# SCH_Jafar_wiredopposite_2022-12-09.net
KiCad netlist of a schematic drawn in EasyEDA
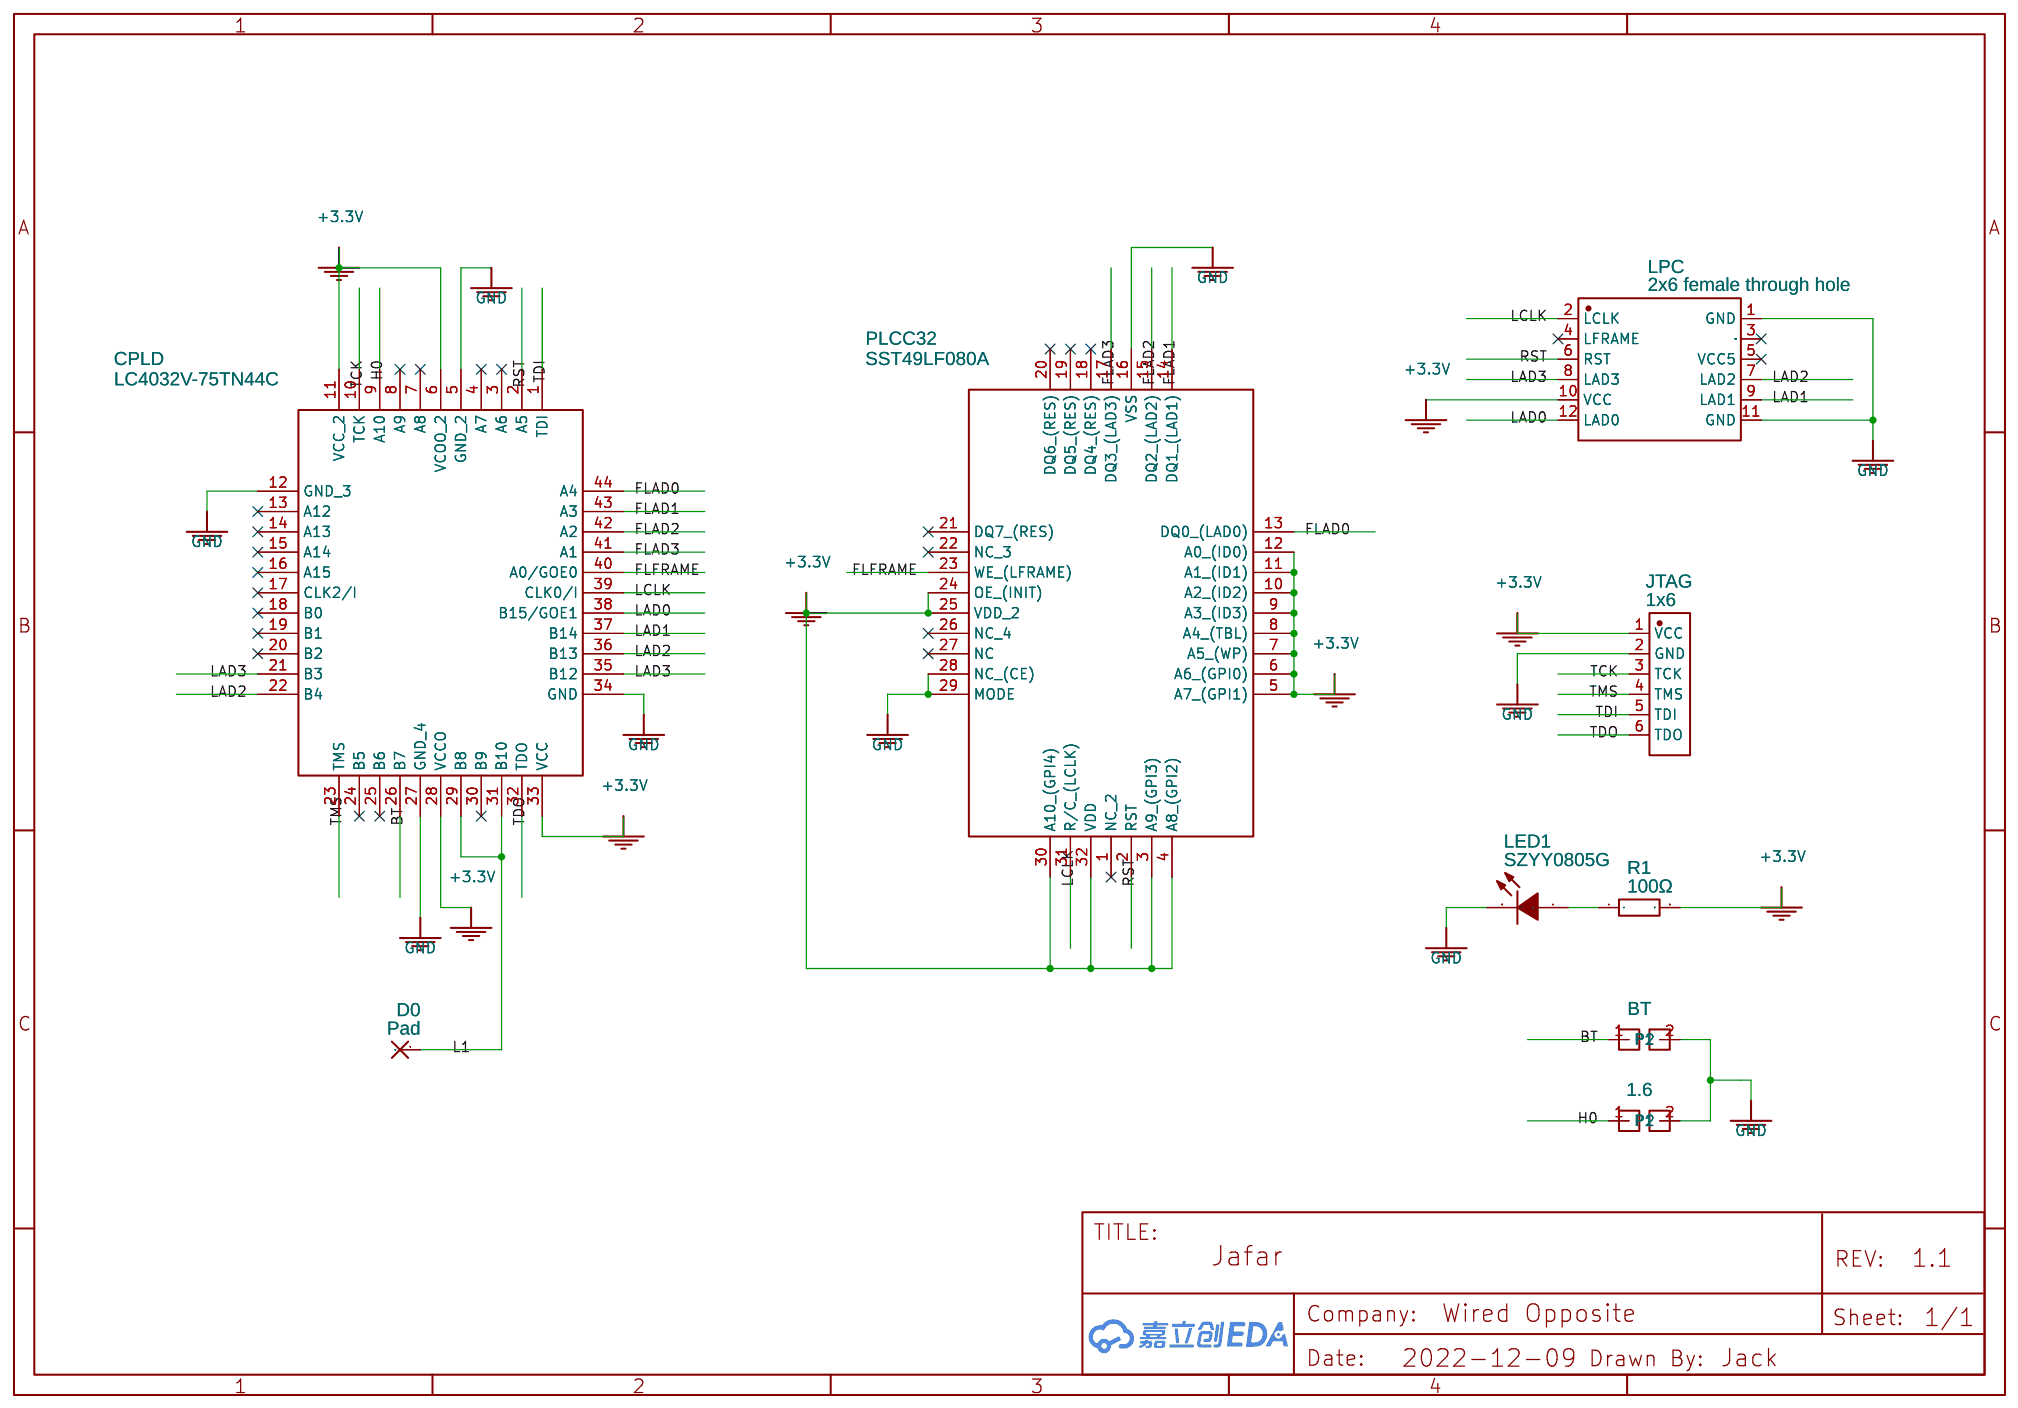
[diagram p0: schematic sheet]

(export (version "E")
  (design (tool "Eeschema 10.0.6"))
  (components
    (comp (ref "1.6") (value "2 PAD WIRE BRIDGE") (libsource (lib "") (part "2 PAD WIRE BRIDGE_1")))
    (comp (ref "BT") (value "2 PAD WIRE BRIDGE") (libsource (lib "") (part "2 PAD WIRE BRIDGE")))
    (comp (ref "CPLD") (value "LC4032V-75TN44C") (libsource (lib "") (part "LC4032V-75TN44C")))
    (comp (ref "D0") (value "Pad") (libsource (lib "") (part "WIREPADSMD5-1,8")))
    (comp (ref "JTAG")
      (value "1x6")
      (fields (field (name "BOM_Manufacturer Part") "HB3106F") (field (name "BOM_Supplier Part") "C2761399"))
      (libsource (lib "") (part "HB3106F"))
    )
    (comp (ref "LED1")
      (value "SZYY0805G")
      (fields (field (name "BOM_Supplier Part") "C434432"))
      (libsource (lib "") (part "SZYY0805G"))
    )
    (comp (ref "LPC") (value "2x6 female through hole") (libsource (lib "") (part "2x6 lpc")))
    (comp (ref "PLCC32")
      (value "SST49LF080A")
      (fields (field (name "BOM_Manufacturer Part") "SST49LF080A-33-4C-NHE"))
      (libsource (lib "") (part "SST49LF080A"))
    )
    (comp (ref "R1")
      (value "100Ω")
      (fields
        (field (name "BOM_Manufacturer Part") "ERA6AEB101V")
        (field (name "BOM_Supplier Part") "C445646")
      )
      (libsource (lib "") (part "ERA6AEB101V"))
    )
  )
  (nets
    (net (code "1") (name "+3.3V") (class "Default")
      (node (ref "CPLD") (pin "11") (pinfunction "VCC_2_11") (pintype "unspecified"))
      (node (ref "CPLD") (pin "28") (pinfunction "VCCO_28") (pintype "unspecified"))
      (node (ref "CPLD") (pin "33") (pinfunction "VCC_33") (pintype "unspecified"))
      (node (ref "CPLD") (pin "6") (pinfunction "VCOO_2_6") (pintype "unspecified"))
      (node (ref "JTAG") (pin "1") (pinfunction "VCC_1") (pintype "unspecified"))
      (node (ref "LPC") (pin "10") (pinfunction "VCC_10") (pintype "unspecified"))
      (node (ref "PLCC32") (pin "10") (pinfunction "A2_(ID2)_10") (pintype "unspecified"))
      (node (ref "PLCC32") (pin "11") (pinfunction "A1_(ID1)_11") (pintype "unspecified"))
      (node (ref "PLCC32") (pin "12") (pinfunction "A0_(ID0)_12") (pintype "unspecified"))
      (node (ref "PLCC32") (pin "24") (pinfunction "OE_(INIT)_24") (pintype "unspecified"))
      (node (ref "PLCC32") (pin "25") (pinfunction "VDD_2_25") (pintype "unspecified"))
      (node (ref "PLCC32") (pin "3") (pinfunction "A9_(GPI3)_3") (pintype "unspecified"))
      (node (ref "PLCC32") (pin "30") (pinfunction "A10_(GPI4)_30") (pintype "unspecified"))
      (node (ref "PLCC32") (pin "32") (pinfunction "VDD_32") (pintype "unspecified"))
      (node (ref "PLCC32") (pin "4") (pinfunction "A8_(GPI2)_4") (pintype "unspecified"))
      (node (ref "PLCC32") (pin "5") (pinfunction "A7_(GPI1)_5") (pintype "unspecified"))
      (node (ref "PLCC32") (pin "6") (pinfunction "A6_(GPI0)_6") (pintype "unspecified"))
      (node (ref "PLCC32") (pin "7") (pinfunction "A5_(WP)_7") (pintype "unspecified"))
      (node (ref "PLCC32") (pin "8") (pinfunction "A4_(TBL)_8") (pintype "unspecified"))
      (node (ref "PLCC32") (pin "9") (pinfunction "A3_(ID3)_9") (pintype "unspecified"))
      (node (ref "R1") (pin "2") (pinfunction "2_2") (pintype "unspecified"))
    )
    (net (code "2") (name "/BT") (class "Default")
      (node (ref "BT") (pin "1") (pinfunction "P1_1") (pintype "unspecified"))
      (node (ref "CPLD") (pin "26") (pinfunction "B7_26") (pintype "unspecified"))
    )
    (net (code "3") (name "/FLAD0") (class "Default")
      (node (ref "CPLD") (pin "44") (pinfunction "A4_44") (pintype "unspecified"))
      (node (ref "PLCC32") (pin "13") (pinfunction "DQ0_(LAD0)_13") (pintype "unspecified"))
    )
    (net (code "4") (name "/FLAD1") (class "Default")
      (node (ref "CPLD") (pin "43") (pinfunction "A3_43") (pintype "unspecified"))
      (node (ref "PLCC32") (pin "14") (pinfunction "DQ1_(LAD1)_14") (pintype "unspecified"))
    )
    (net (code "5") (name "/FLAD2") (class "Default")
      (node (ref "CPLD") (pin "42") (pinfunction "A2_42") (pintype "unspecified"))
      (node (ref "PLCC32") (pin "15") (pinfunction "DQ2_(LAD2)_15") (pintype "unspecified"))
    )
    (net (code "6") (name "/FLAD3") (class "Default")
      (node (ref "CPLD") (pin "41") (pinfunction "A1_41") (pintype "unspecified"))
      (node (ref "PLCC32") (pin "17") (pinfunction "DQ3_(LAD3)_17") (pintype "unspecified"))
    )
    (net (code "7") (name "/FLFRAME") (class "Default")
      (node (ref "CPLD") (pin "40") (pinfunction "A0/GOE0_40") (pintype "unspecified"))
      (node (ref "PLCC32") (pin "23") (pinfunction "WE_(LFRAME)_23") (pintype "unspecified"))
    )
    (net (code "8") (name "/H0") (class "Default")
      (node (ref "1.6") (pin "1") (pinfunction "P1_1") (pintype "unspecified"))
      (node (ref "CPLD") (pin "9") (pinfunction "A10_9") (pintype "unspecified"))
    )
    (net (code "9") (name "/L1") (class "Default")
      (node (ref "CPLD") (pin "29") (pinfunction "B8_29") (pintype "unspecified"))
      (node (ref "CPLD") (pin "31") (pinfunction "B10_31") (pintype "unspecified"))
      (node (ref "D0") (pin "1") (pinfunction "P_1") (pintype "bidirectional"))
    )
    (net (code "10") (name "/LAD0") (class "Default")
      (node (ref "CPLD") (pin "38") (pinfunction "B15/GOE1_38") (pintype "unspecified"))
      (node (ref "LPC") (pin "12") (pinfunction "LAD0_12") (pintype "unspecified"))
    )
    (net (code "11") (name "/LAD1") (class "Default")
      (node (ref "CPLD") (pin "37") (pinfunction "B14_37") (pintype "unspecified"))
      (node (ref "LPC") (pin "9") (pinfunction "LAD1_9") (pintype "unspecified"))
    )
    (net (code "12") (name "/LAD2") (class "Default")
      (node (ref "CPLD") (pin "22") (pinfunction "B4_22") (pintype "unspecified"))
      (node (ref "CPLD") (pin "36") (pinfunction "B13_36") (pintype "unspecified"))
      (node (ref "LPC") (pin "7") (pinfunction "LAD2_7") (pintype "unspecified"))
    )
    (net (code "13") (name "/LAD3") (class "Default")
      (node (ref "CPLD") (pin "21") (pinfunction "B3_21") (pintype "unspecified"))
      (node (ref "CPLD") (pin "35") (pinfunction "B12_35") (pintype "unspecified"))
      (node (ref "LPC") (pin "8") (pinfunction "LAD3_8") (pintype "unspecified"))
    )
    (net (code "14") (name "/LCLK") (class "Default")
      (node (ref "CPLD") (pin "39") (pinfunction "CLK0/I_39") (pintype "unspecified"))
      (node (ref "LPC") (pin "2") (pinfunction "LCLK_2") (pintype "unspecified"))
      (node (ref "PLCC32") (pin "31") (pinfunction "R/C_(LCLK)_31") (pintype "unspecified"))
    )
    (net (code "15") (name "/RST") (class "Default")
      (node (ref "CPLD") (pin "2") (pinfunction "A5_2") (pintype "unspecified"))
      (node (ref "LPC") (pin "6") (pinfunction "RST_6") (pintype "unspecified"))
      (node (ref "PLCC32") (pin "2") (pinfunction "RST_2") (pintype "unspecified"))
    )
    (net (code "16") (name "/TCK") (class "Default")
      (node (ref "CPLD") (pin "10") (pinfunction "TCK_10") (pintype "unspecified"))
      (node (ref "JTAG") (pin "3") (pinfunction "TCK_3") (pintype "unspecified"))
    )
    (net (code "17") (name "/TDI") (class "Default")
      (node (ref "CPLD") (pin "1") (pinfunction "TDI_1") (pintype "unspecified"))
      (node (ref "JTAG") (pin "5") (pinfunction "TDI_5") (pintype "unspecified"))
    )
    (net (code "18") (name "/TDO") (class "Default")
      (node (ref "CPLD") (pin "32") (pinfunction "TDO_32") (pintype "unspecified"))
      (node (ref "JTAG") (pin "6") (pinfunction "TDO_6") (pintype "unspecified"))
    )
    (net (code "19") (name "/TMS") (class "Default")
      (node (ref "CPLD") (pin "23") (pinfunction "TMS_23") (pintype "unspecified"))
      (node (ref "JTAG") (pin "4") (pinfunction "TMS_4") (pintype "unspecified"))
    )
    (net (code "20") (name "GND") (class "Default")
      (node (ref "1.6") (pin "2") (pinfunction "P2_2") (pintype "unspecified"))
      (node (ref "BT") (pin "2") (pinfunction "P2_2") (pintype "unspecified"))
      (node (ref "CPLD") (pin "12") (pinfunction "GND_3_12") (pintype "unspecified"))
      (node (ref "CPLD") (pin "27") (pinfunction "GND_4_27") (pintype "unspecified"))
      (node (ref "CPLD") (pin "34") (pinfunction "GND_34") (pintype "unspecified"))
      (node (ref "CPLD") (pin "5") (pinfunction "GND_2_5") (pintype "unspecified"))
      (node (ref "JTAG") (pin "2") (pinfunction "GND_2") (pintype "unspecified"))
      (node (ref "LED1") (pin "2") (pinfunction "-_2") (pintype "unspecified"))
      (node (ref "LPC") (pin "1") (pinfunction "GND_1") (pintype "unspecified"))
      (node (ref "LPC") (pin "11") (pinfunction "GND_11") (pintype "unspecified"))
      (node (ref "PLCC32") (pin "16") (pinfunction "VSS_16") (pintype "unspecified"))
      (node (ref "PLCC32") (pin "28") (pinfunction "NC_(CE)_28") (pintype "unspecified"))
      (node (ref "PLCC32") (pin "29") (pinfunction "MODE_29") (pintype "unspecified"))
    )
    (net (code "21") (name "Net-(LED1-+)") (class "Default")
      (node (ref "LED1") (pin "1") (pinfunction "+_1") (pintype "unspecified"))
      (node (ref "R1") (pin "1") (pinfunction "1_1") (pintype "unspecified"))
    )
    (net (code "22") (name "unconnected-(CPLD-A6-Pad3)") (class "Default")
      (node (ref "CPLD") (pin "3") (pinfunction "A6_3") (pintype "unspecified+no_connect"))
    )
    (net (code "23") (name "unconnected-(CPLD-A7-Pad4)") (class "Default")
      (node (ref "CPLD") (pin "4") (pinfunction "A7_4") (pintype "unspecified+no_connect"))
    )
    (net (code "24") (name "unconnected-(CPLD-A8-Pad7)") (class "Default")
      (node (ref "CPLD") (pin "7") (pinfunction "A8_7") (pintype "unspecified+no_connect"))
    )
    (net (code "25") (name "unconnected-(CPLD-A9-Pad8)") (class "Default")
      (node (ref "CPLD") (pin "8") (pinfunction "A9_8") (pintype "unspecified+no_connect"))
    )
    (net (code "26") (name "unconnected-(CPLD-A12-Pad13)") (class "Default")
      (node (ref "CPLD") (pin "13") (pinfunction "A12_13") (pintype "unspecified+no_connect"))
    )
    (net (code "27") (name "unconnected-(CPLD-A13-Pad14)") (class "Default")
      (node (ref "CPLD") (pin "14") (pinfunction "A13_14") (pintype "unspecified+no_connect"))
    )
    (net (code "28") (name "unconnected-(CPLD-A14-Pad15)") (class "Default")
      (node (ref "CPLD") (pin "15") (pinfunction "A14_15") (pintype "unspecified+no_connect"))
    )
    (net (code "29") (name "unconnected-(CPLD-A15-Pad16)") (class "Default")
      (node (ref "CPLD") (pin "16") (pinfunction "A15_16") (pintype "unspecified+no_connect"))
    )
    (net (code "30") (name "unconnected-(CPLD-B0-Pad18)") (class "Default")
      (node (ref "CPLD") (pin "18") (pinfunction "B0_18") (pintype "unspecified+no_connect"))
    )
    (net (code "31") (name "unconnected-(CPLD-B1-Pad19)") (class "Default")
      (node (ref "CPLD") (pin "19") (pinfunction "B1_19") (pintype "unspecified+no_connect"))
    )
    (net (code "32") (name "unconnected-(CPLD-B2-Pad20)") (class "Default")
      (node (ref "CPLD") (pin "20") (pinfunction "B2_20") (pintype "unspecified+no_connect"))
    )
    (net (code "33") (name "unconnected-(CPLD-B5-Pad24)") (class "Default")
      (node (ref "CPLD") (pin "24") (pinfunction "B5_24") (pintype "unspecified+no_connect"))
    )
    (net (code "34") (name "unconnected-(CPLD-B6-Pad25)") (class "Default")
      (node (ref "CPLD") (pin "25") (pinfunction "B6_25") (pintype "unspecified+no_connect"))
    )
    (net (code "35") (name "unconnected-(CPLD-B9-Pad30)") (class "Default")
      (node (ref "CPLD") (pin "30") (pinfunction "B9_30") (pintype "unspecified+no_connect"))
    )
    (net (code "36") (name "unconnected-(CPLD-CLK2{slash}I-Pad17)") (class "Default")
      (node (ref "CPLD") (pin "17") (pinfunction "CLK2/I_17") (pintype "unspecified+no_connect"))
    )
    (net (code "37") (name "unconnected-(LPC-LFRAME-Pad4)") (class "Default")
      (node (ref "LPC") (pin "4") (pinfunction "LFRAME_4") (pintype "unspecified+no_connect"))
    )
    (net (code "38") (name "unconnected-(LPC-NONE-Pad3)") (class "Default")
      (node (ref "LPC") (pin "3") (pinfunction "NONE_3") (pintype "unspecified+no_connect"))
    )
    (net (code "39") (name "unconnected-(LPC-VCC5-Pad5)") (class "Default")
      (node (ref "LPC") (pin "5") (pinfunction "VCC5_5") (pintype "unspecified+no_connect"))
    )
    (net (code "40") (name "unconnected-(PLCC32-DQ4_(RES)-Pad18)") (class "Default")
      (node (ref "PLCC32") (pin "18") (pinfunction "DQ4_(RES)_18") (pintype "unspecified+no_connect"))
    )
    (net (code "41") (name "unconnected-(PLCC32-DQ5_(RES)-Pad19)") (class "Default")
      (node (ref "PLCC32") (pin "19") (pinfunction "DQ5_(RES)_19") (pintype "unspecified+no_connect"))
    )
    (net (code "42") (name "unconnected-(PLCC32-DQ6_(RES)-Pad20)") (class "Default")
      (node (ref "PLCC32") (pin "20") (pinfunction "DQ6_(RES)_20") (pintype "unspecified+no_connect"))
    )
    (net (code "43") (name "unconnected-(PLCC32-DQ7_(RES)-Pad21)") (class "Default")
      (node (ref "PLCC32") (pin "21") (pinfunction "DQ7_(RES)_21") (pintype "unspecified+no_connect"))
    )
    (net (code "44") (name "unconnected-(PLCC32-NC-Pad27)") (class "Default")
      (node (ref "PLCC32") (pin "27") (pinfunction "NC_27") (pintype "unspecified+no_connect"))
    )
    (net (code "45") (name "unconnected-(PLCC32-NC_2-Pad1)") (class "Default")
      (node (ref "PLCC32") (pin "1") (pinfunction "NC_2_1") (pintype "unspecified+no_connect"))
    )
    (net (code "46") (name "unconnected-(PLCC32-NC_3-Pad22)") (class "Default")
      (node (ref "PLCC32") (pin "22") (pinfunction "NC_3_22") (pintype "unspecified+no_connect"))
    )
    (net (code "47") (name "unconnected-(PLCC32-NC_4-Pad26)") (class "Default")
      (node (ref "PLCC32") (pin "26") (pinfunction "NC_4_26") (pintype "unspecified+no_connect"))
    )
  )
)
